# L3G4200D-Breakout-v10.net
KiCad netlist of a schematic drawn in EAGLE
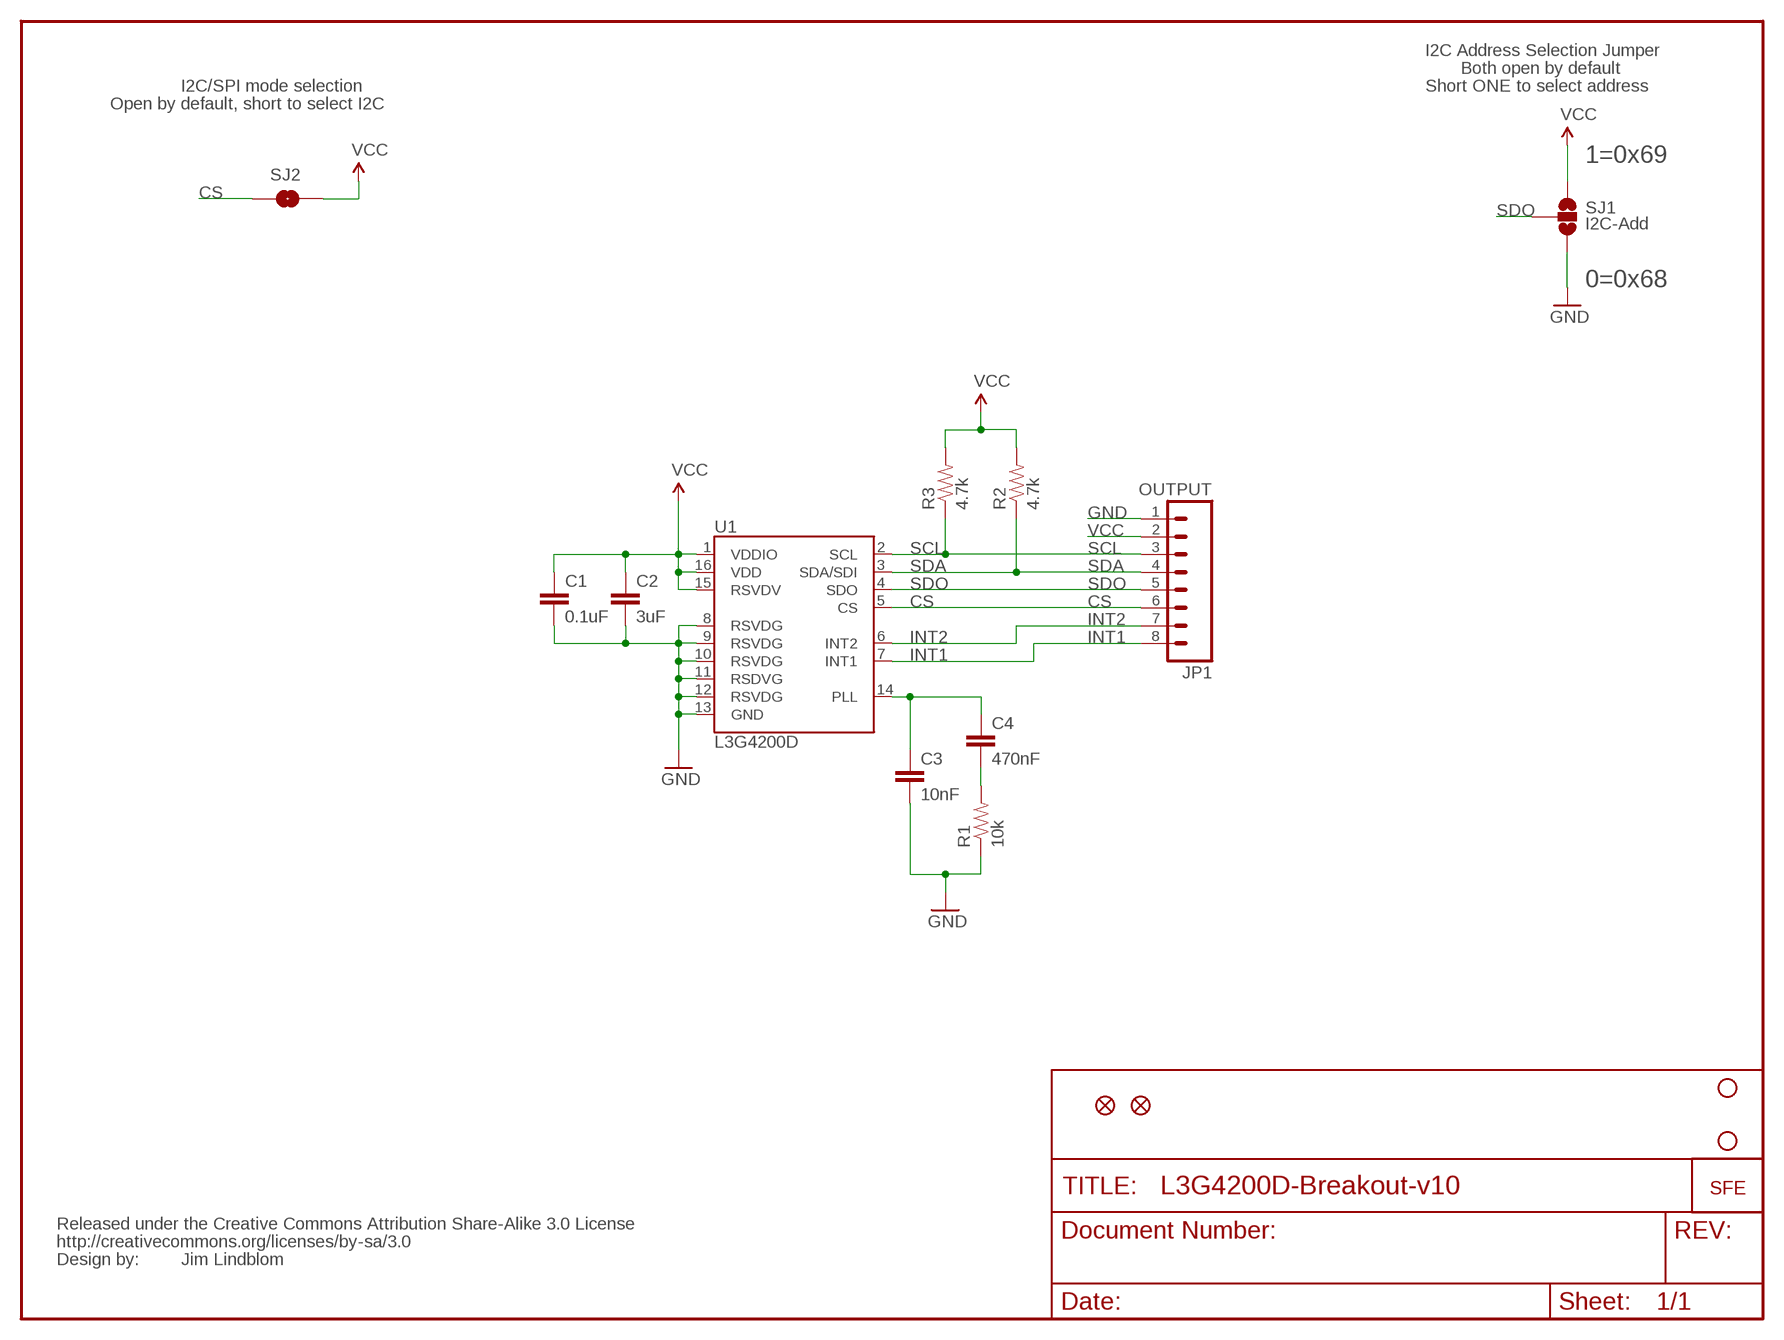
[diagram p0: schematic, sheet 1]

(export (version "E")
  (design (tool "Eeschema 10.0.6"))
  (components
    (comp (ref "C1")
      (value "0.1uF")
      (footprint "eagle-import:0603-CAP")
      (libsource (lib "eagle-import") (part "CAP0603-CAP"))
    )
    (comp (ref "C2")
      (value "3uF")
      (footprint "eagle-import:0603-CAP")
      (libsource (lib "eagle-import") (part "CAP0603-CAP"))
    )
    (comp (ref "C3")
      (value "10nF")
      (footprint "eagle-import:0603-CAP")
      (libsource (lib "eagle-import") (part "CAP0603-CAP"))
    )
    (comp (ref "C4")
      (value "470nF")
      (footprint "eagle-import:0603-CAP")
      (libsource (lib "eagle-import") (part "CAP0603-CAP"))
    )
    (comp (ref "JP1")
      (value "OUTPUT")
      (footprint "eagle-import:1X08")
      (libsource (lib "eagle-import") (part "M08"))
    )
    (comp (ref "JP2")
      (value "STAND-OFF")
      (footprint "eagle-import:STAND-OFF")
      (libsource (lib "eagle-import") (part "STAND-OFF"))
    )
    (comp (ref "JP3")
      (value "STAND-OFF")
      (footprint "eagle-import:STAND-OFF")
      (libsource (lib "eagle-import") (part "STAND-OFF"))
    )
    (comp (ref "JP4")
      (value "LOGO-SFESK")
      (footprint "eagle-import:SFE-LOGO-FLAME")
      (libsource (lib "eagle-import") (part "LOGO-SFESK"))
    )
    (comp (ref "JP5")
      (value "FIDUCIAL1X2")
      (footprint "eagle-import:FIDUCIAL-1X2")
      (libsource (lib "eagle-import") (part "FIDUCIAL1X2"))
    )
    (comp (ref "JP6")
      (value "FIDUCIAL1X2")
      (footprint "eagle-import:FIDUCIAL-1X2")
      (libsource (lib "eagle-import") (part "FIDUCIAL1X2"))
    )
    (comp (ref "R1")
      (value "10k")
      (footprint "eagle-import:0603-RES")
      (libsource (lib "eagle-import") (part "RESISTOR0603-RES"))
    )
    (comp (ref "R2")
      (value "4.7k")
      (footprint "eagle-import:0603-RES")
      (libsource (lib "eagle-import") (part "RESISTOR0603-RES"))
    )
    (comp (ref "R3")
      (value "4.7k")
      (footprint "eagle-import:0603-RES")
      (libsource (lib "eagle-import") (part "RESISTOR0603-RES"))
    )
    (comp (ref "SJ1")
      (value "I2C-Add")
      (footprint "eagle-import:SJ_3")
      (libsource (lib "eagle-import") (part "SOLDERJUMPER_2WAYS"))
    )
    (comp (ref "SJ2")
      (value "I2C-Mode")
      (footprint "eagle-import:SJ_2S-NO")
      (libsource (lib "eagle-import") (part "SOLDERJUMPERNO"))
    )
    (comp (ref "U$1")
      (value "CREATIVE_COMMONS")
      (footprint "eagle-import:CREATIVE_COMMONS")
      (libsource (lib "eagle-import") (part "CREATIVE_COMMONS"))
    )
    (comp (ref "U1")
      (value "L3G4200D")
      (footprint "eagle-import:LGA16-4X4")
      (libsource (lib "eagle-import") (part "L3G4200D"))
    )
  )
  (nets
    (net (code "1") (name "/CS") (class "Default")
      (node (ref "JP1") (pin "6") (pinfunction "6_6") (pintype "passive"))
      (node (ref "SJ2") (pin "1") (pinfunction "1_1") (pintype "passive"))
      (node (ref "U1") (pin "5") (pinfunction "CS_5") (pintype "bidirectional"))
    )
    (net (code "2") (name "/INT1") (class "Default")
      (node (ref "JP1") (pin "8") (pinfunction "8_8") (pintype "passive"))
      (node (ref "U1") (pin "7") (pinfunction "INT1_7") (pintype "bidirectional"))
    )
    (net (code "3") (name "/INT2") (class "Default")
      (node (ref "JP1") (pin "7") (pinfunction "7_7") (pintype "passive"))
      (node (ref "U1") (pin "6") (pinfunction "INT2_6") (pintype "bidirectional"))
    )
    (net (code "4") (name "/SCL") (class "Default")
      (node (ref "JP1") (pin "3") (pinfunction "3_3") (pintype "passive"))
      (node (ref "R3") (pin "1") (pinfunction "1_1") (pintype "passive"))
      (node (ref "U1") (pin "2") (pinfunction "SCL_2") (pintype "bidirectional"))
    )
    (net (code "5") (name "/SDA") (class "Default")
      (node (ref "JP1") (pin "4") (pinfunction "4_4") (pintype "passive"))
      (node (ref "R2") (pin "1") (pinfunction "1_1") (pintype "passive"))
      (node (ref "U1") (pin "3") (pinfunction "SDA/SDI_3") (pintype "bidirectional"))
    )
    (net (code "6") (name "/SDO") (class "Default")
      (node (ref "JP1") (pin "5") (pinfunction "5_5") (pintype "passive"))
      (node (ref "SJ1") (pin "2") (pinfunction "2_2") (pintype "passive"))
      (node (ref "U1") (pin "4") (pinfunction "SDO_4") (pintype "bidirectional"))
    )
    (net (code "7") (name "GND") (class "Default")
      (node (ref "C1") (pin "2") (pinfunction "2_2") (pintype "passive"))
      (node (ref "C2") (pin "2") (pinfunction "2_2") (pintype "passive"))
      (node (ref "C3") (pin "2") (pinfunction "2_2") (pintype "passive"))
      (node (ref "JP1") (pin "1") (pinfunction "1_1") (pintype "passive"))
      (node (ref "R1") (pin "1") (pinfunction "1_1") (pintype "passive"))
      (node (ref "SJ1") (pin "3") (pinfunction "3_3") (pintype "passive"))
      (node (ref "U1") (pin "10") (pinfunction "RSVDG_10") (pintype "bidirectional"))
      (node (ref "U1") (pin "11") (pinfunction "RSDVG_11") (pintype "bidirectional"))
      (node (ref "U1") (pin "12") (pinfunction "RSVDG_12") (pintype "bidirectional"))
      (node (ref "U1") (pin "13") (pinfunction "GND_13") (pintype "bidirectional"))
      (node (ref "U1") (pin "8") (pinfunction "RSVDG_8") (pintype "bidirectional"))
      (node (ref "U1") (pin "9") (pinfunction "RSVDG_9") (pintype "bidirectional"))
    )
    (net (code "8") (name "Net-(C4-Pad2)") (class "Default")
      (node (ref "C4") (pin "2") (pinfunction "2_2") (pintype "passive"))
      (node (ref "R1") (pin "2") (pinfunction "2_2") (pintype "passive"))
    )
    (net (code "9") (name "Net-(U1-PLL)") (class "Default")
      (node (ref "C3") (pin "1") (pinfunction "1_1") (pintype "passive"))
      (node (ref "C4") (pin "1") (pinfunction "1_1") (pintype "passive"))
      (node (ref "U1") (pin "14") (pinfunction "PLL_14") (pintype "bidirectional"))
    )
    (net (code "10") (name "VCC") (class "Default")
      (node (ref "C1") (pin "1") (pinfunction "1_1") (pintype "passive"))
      (node (ref "C2") (pin "1") (pinfunction "1_1") (pintype "passive"))
      (node (ref "JP1") (pin "2") (pinfunction "2_2") (pintype "passive"))
      (node (ref "R2") (pin "2") (pinfunction "2_2") (pintype "passive"))
      (node (ref "R3") (pin "2") (pinfunction "2_2") (pintype "passive"))
      (node (ref "SJ1") (pin "1") (pinfunction "1_1") (pintype "passive"))
      (node (ref "SJ2") (pin "2") (pinfunction "2_2") (pintype "passive"))
      (node (ref "U1") (pin "1") (pinfunction "VDDIO_1") (pintype "bidirectional"))
      (node (ref "U1") (pin "15") (pinfunction "RSVDV_15") (pintype "bidirectional"))
      (node (ref "U1") (pin "16") (pinfunction "VDD_16") (pintype "bidirectional"))
    )
  )
)
